# Current_Sinks.net
KiCad netlist of a schematic drawn in Altium Designer
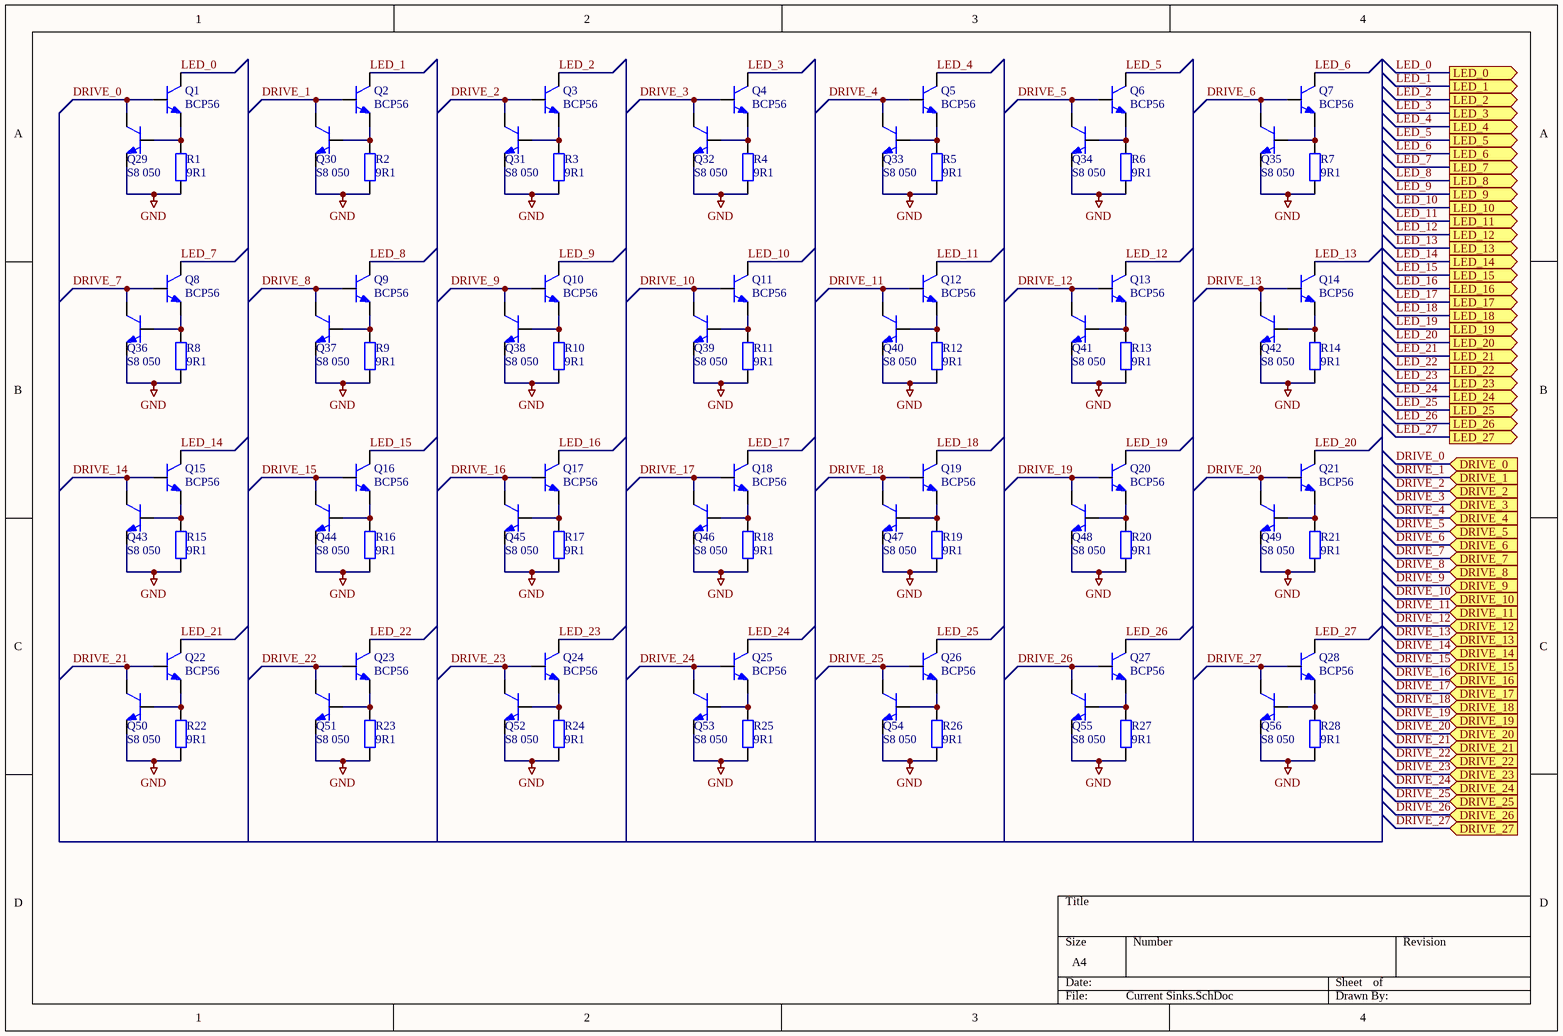
[diagram p0: Current Sinks.SchDoc]

(export (version "E")
  (design (tool "Eeschema 10.0.6"))
  (components
    (comp (ref "Q1")
      (value "BCP56")
      (footprint "SOT223")
      (description "BCP56 80 V, 1 A NPN medium power transistors")
      (libsource (lib "LED TAIL LIGHTS") (part "NPN"))
    )
    (comp (ref "Q2")
      (value "BCP56")
      (footprint "SOT223")
      (description "BCP56 80 V, 1 A NPN medium power transistors")
      (libsource (lib "LED TAIL LIGHTS") (part "NPN"))
    )
    (comp (ref "Q3")
      (value "BCP56")
      (footprint "SOT223")
      (description "BCP56 80 V, 1 A NPN medium power transistors")
      (libsource (lib "LED TAIL LIGHTS") (part "NPN"))
    )
    (comp (ref "Q4")
      (value "BCP56")
      (footprint "SOT223")
      (description "BCP56 80 V, 1 A NPN medium power transistors")
      (libsource (lib "LED TAIL LIGHTS") (part "NPN"))
    )
    (comp (ref "Q5")
      (value "BCP56")
      (footprint "SOT223")
      (description "BCP56 80 V, 1 A NPN medium power transistors")
      (libsource (lib "LED TAIL LIGHTS") (part "NPN"))
    )
    (comp (ref "Q6")
      (value "BCP56")
      (footprint "SOT223")
      (description "BCP56 80 V, 1 A NPN medium power transistors")
      (libsource (lib "LED TAIL LIGHTS") (part "NPN"))
    )
    (comp (ref "Q7")
      (value "BCP56")
      (footprint "SOT223")
      (description "BCP56 80 V, 1 A NPN medium power transistors")
      (libsource (lib "LED TAIL LIGHTS") (part "NPN"))
    )
    (comp (ref "Q8")
      (value "BCP56")
      (footprint "SOT223")
      (description "BCP56 80 V, 1 A NPN medium power transistors")
      (libsource (lib "LED TAIL LIGHTS") (part "NPN"))
    )
    (comp (ref "Q9")
      (value "BCP56")
      (footprint "SOT223")
      (description "BCP56 80 V, 1 A NPN medium power transistors")
      (libsource (lib "LED TAIL LIGHTS") (part "NPN"))
    )
    (comp (ref "Q10")
      (value "BCP56")
      (footprint "SOT223")
      (description "BCP56 80 V, 1 A NPN medium power transistors")
      (libsource (lib "LED TAIL LIGHTS") (part "NPN"))
    )
    (comp (ref "Q11")
      (value "BCP56")
      (footprint "SOT223")
      (description "BCP56 80 V, 1 A NPN medium power transistors")
      (libsource (lib "LED TAIL LIGHTS") (part "NPN"))
    )
    (comp (ref "Q12")
      (value "BCP56")
      (footprint "SOT223")
      (description "BCP56 80 V, 1 A NPN medium power transistors")
      (libsource (lib "LED TAIL LIGHTS") (part "NPN"))
    )
    (comp (ref "Q13")
      (value "BCP56")
      (footprint "SOT223")
      (description "BCP56 80 V, 1 A NPN medium power transistors")
      (libsource (lib "LED TAIL LIGHTS") (part "NPN"))
    )
    (comp (ref "Q14")
      (value "BCP56")
      (footprint "SOT223")
      (description "BCP56 80 V, 1 A NPN medium power transistors")
      (libsource (lib "LED TAIL LIGHTS") (part "NPN"))
    )
    (comp (ref "Q15")
      (value "BCP56")
      (footprint "SOT223")
      (description "BCP56 80 V, 1 A NPN medium power transistors")
      (libsource (lib "LED TAIL LIGHTS") (part "NPN"))
    )
    (comp (ref "Q16")
      (value "BCP56")
      (footprint "SOT223")
      (description "BCP56 80 V, 1 A NPN medium power transistors")
      (libsource (lib "LED TAIL LIGHTS") (part "NPN"))
    )
    (comp (ref "Q17")
      (value "BCP56")
      (footprint "SOT223")
      (description "BCP56 80 V, 1 A NPN medium power transistors")
      (libsource (lib "LED TAIL LIGHTS") (part "NPN"))
    )
    (comp (ref "Q18")
      (value "BCP56")
      (footprint "SOT223")
      (description "BCP56 80 V, 1 A NPN medium power transistors")
      (libsource (lib "LED TAIL LIGHTS") (part "NPN"))
    )
    (comp (ref "Q19")
      (value "BCP56")
      (footprint "SOT223")
      (description "BCP56 80 V, 1 A NPN medium power transistors")
      (libsource (lib "LED TAIL LIGHTS") (part "NPN"))
    )
    (comp (ref "Q20")
      (value "BCP56")
      (footprint "SOT223")
      (description "BCP56 80 V, 1 A NPN medium power transistors")
      (libsource (lib "LED TAIL LIGHTS") (part "NPN"))
    )
    (comp (ref "Q21")
      (value "BCP56")
      (footprint "SOT223")
      (description "BCP56 80 V, 1 A NPN medium power transistors")
      (libsource (lib "LED TAIL LIGHTS") (part "NPN"))
    )
    (comp (ref "Q22")
      (value "BCP56")
      (footprint "SOT223")
      (description "BCP56 80 V, 1 A NPN medium power transistors")
      (libsource (lib "LED TAIL LIGHTS") (part "NPN"))
    )
    (comp (ref "Q23")
      (value "BCP56")
      (footprint "SOT223")
      (description "BCP56 80 V, 1 A NPN medium power transistors")
      (libsource (lib "LED TAIL LIGHTS") (part "NPN"))
    )
    (comp (ref "Q24")
      (value "BCP56")
      (footprint "SOT223")
      (description "BCP56 80 V, 1 A NPN medium power transistors")
      (libsource (lib "LED TAIL LIGHTS") (part "NPN"))
    )
    (comp (ref "Q25")
      (value "BCP56")
      (footprint "SOT223")
      (description "BCP56 80 V, 1 A NPN medium power transistors")
      (libsource (lib "LED TAIL LIGHTS") (part "NPN"))
    )
    (comp (ref "Q26")
      (value "BCP56")
      (footprint "SOT223")
      (description "BCP56 80 V, 1 A NPN medium power transistors")
      (libsource (lib "LED TAIL LIGHTS") (part "NPN"))
    )
    (comp (ref "Q27")
      (value "BCP56")
      (footprint "SOT223")
      (description "BCP56 80 V, 1 A NPN medium power transistors")
      (libsource (lib "LED TAIL LIGHTS") (part "NPN"))
    )
    (comp (ref "Q28")
      (value "BCP56")
      (footprint "SOT223")
      (description "BCP56 80 V, 1 A NPN medium power transistors")
      (libsource (lib "LED TAIL LIGHTS") (part "NPN"))
    )
    (comp (ref "Q29")
      (value "S8 050")
      (footprint "SOT23-3L")
      (description "BCP56 80 V, 1 A NPN medium power transistors")
      (libsource (lib "LED TAIL LIGHTS") (part "NPN"))
    )
    (comp (ref "Q30")
      (value "S8 050")
      (footprint "SOT23-3L")
      (description "BCP56 80 V, 1 A NPN medium power transistors")
      (libsource (lib "LED TAIL LIGHTS") (part "NPN"))
    )
    (comp (ref "Q31")
      (value "S8 050")
      (footprint "SOT23-3L")
      (description "BCP56 80 V, 1 A NPN medium power transistors")
      (libsource (lib "LED TAIL LIGHTS") (part "NPN"))
    )
    (comp (ref "Q32")
      (value "S8 050")
      (footprint "SOT23-3L")
      (description "BCP56 80 V, 1 A NPN medium power transistors")
      (libsource (lib "LED TAIL LIGHTS") (part "NPN"))
    )
    (comp (ref "Q33")
      (value "S8 050")
      (footprint "SOT23-3L")
      (description "BCP56 80 V, 1 A NPN medium power transistors")
      (libsource (lib "LED TAIL LIGHTS") (part "NPN"))
    )
    (comp (ref "Q34")
      (value "S8 050")
      (footprint "SOT23-3L")
      (description "BCP56 80 V, 1 A NPN medium power transistors")
      (libsource (lib "LED TAIL LIGHTS") (part "NPN"))
    )
    (comp (ref "Q35")
      (value "S8 050")
      (footprint "SOT23-3L")
      (description "BCP56 80 V, 1 A NPN medium power transistors")
      (libsource (lib "LED TAIL LIGHTS") (part "NPN"))
    )
    (comp (ref "Q36")
      (value "S8 050")
      (footprint "SOT23-3L")
      (description "BCP56 80 V, 1 A NPN medium power transistors")
      (libsource (lib "LED TAIL LIGHTS") (part "NPN"))
    )
    (comp (ref "Q37")
      (value "S8 050")
      (footprint "SOT23-3L")
      (description "BCP56 80 V, 1 A NPN medium power transistors")
      (libsource (lib "LED TAIL LIGHTS") (part "NPN"))
    )
    (comp (ref "Q38")
      (value "S8 050")
      (footprint "SOT23-3L")
      (description "BCP56 80 V, 1 A NPN medium power transistors")
      (libsource (lib "LED TAIL LIGHTS") (part "NPN"))
    )
    (comp (ref "Q39")
      (value "S8 050")
      (footprint "SOT23-3L")
      (description "BCP56 80 V, 1 A NPN medium power transistors")
      (libsource (lib "LED TAIL LIGHTS") (part "NPN"))
    )
    (comp (ref "Q40")
      (value "S8 050")
      (footprint "SOT23-3L")
      (description "BCP56 80 V, 1 A NPN medium power transistors")
      (libsource (lib "LED TAIL LIGHTS") (part "NPN"))
    )
    (comp (ref "Q41")
      (value "S8 050")
      (footprint "SOT23-3L")
      (description "BCP56 80 V, 1 A NPN medium power transistors")
      (libsource (lib "LED TAIL LIGHTS") (part "NPN"))
    )
    (comp (ref "Q42")
      (value "S8 050")
      (footprint "SOT23-3L")
      (description "BCP56 80 V, 1 A NPN medium power transistors")
      (libsource (lib "LED TAIL LIGHTS") (part "NPN"))
    )
    (comp (ref "Q43")
      (value "S8 050")
      (footprint "SOT23-3L")
      (description "BCP56 80 V, 1 A NPN medium power transistors")
      (libsource (lib "LED TAIL LIGHTS") (part "NPN"))
    )
    (comp (ref "Q44")
      (value "S8 050")
      (footprint "SOT23-3L")
      (description "BCP56 80 V, 1 A NPN medium power transistors")
      (libsource (lib "LED TAIL LIGHTS") (part "NPN"))
    )
    (comp (ref "Q45")
      (value "S8 050")
      (footprint "SOT23-3L")
      (description "BCP56 80 V, 1 A NPN medium power transistors")
      (libsource (lib "LED TAIL LIGHTS") (part "NPN"))
    )
    (comp (ref "Q46")
      (value "S8 050")
      (footprint "SOT23-3L")
      (description "BCP56 80 V, 1 A NPN medium power transistors")
      (libsource (lib "LED TAIL LIGHTS") (part "NPN"))
    )
    (comp (ref "Q47")
      (value "S8 050")
      (footprint "SOT23-3L")
      (description "BCP56 80 V, 1 A NPN medium power transistors")
      (libsource (lib "LED TAIL LIGHTS") (part "NPN"))
    )
    (comp (ref "Q48")
      (value "S8 050")
      (footprint "SOT23-3L")
      (description "BCP56 80 V, 1 A NPN medium power transistors")
      (libsource (lib "LED TAIL LIGHTS") (part "NPN"))
    )
    (comp (ref "Q49")
      (value "S8 050")
      (footprint "SOT23-3L")
      (description "BCP56 80 V, 1 A NPN medium power transistors")
      (libsource (lib "LED TAIL LIGHTS") (part "NPN"))
    )
    (comp (ref "Q50")
      (value "S8 050")
      (footprint "SOT23-3L")
      (description "BCP56 80 V, 1 A NPN medium power transistors")
      (libsource (lib "LED TAIL LIGHTS") (part "NPN"))
    )
    (comp (ref "Q51")
      (value "S8 050")
      (footprint "SOT23-3L")
      (description "BCP56 80 V, 1 A NPN medium power transistors")
      (libsource (lib "LED TAIL LIGHTS") (part "NPN"))
    )
    (comp (ref "Q52")
      (value "S8 050")
      (footprint "SOT23-3L")
      (description "BCP56 80 V, 1 A NPN medium power transistors")
      (libsource (lib "LED TAIL LIGHTS") (part "NPN"))
    )
    (comp (ref "Q53")
      (value "S8 050")
      (footprint "SOT23-3L")
      (description "BCP56 80 V, 1 A NPN medium power transistors")
      (libsource (lib "LED TAIL LIGHTS") (part "NPN"))
    )
    (comp (ref "Q54")
      (value "S8 050")
      (footprint "SOT23-3L")
      (description "BCP56 80 V, 1 A NPN medium power transistors")
      (libsource (lib "LED TAIL LIGHTS") (part "NPN"))
    )
    (comp (ref "Q55")
      (value "S8 050")
      (footprint "SOT23-3L")
      (description "BCP56 80 V, 1 A NPN medium power transistors")
      (libsource (lib "LED TAIL LIGHTS") (part "NPN"))
    )
    (comp (ref "Q56")
      (value "S8 050")
      (footprint "SOT23-3L")
      (description "BCP56 80 V, 1 A NPN medium power transistors")
      (libsource (lib "LED TAIL LIGHTS") (part "NPN"))
    )
    (comp (ref "R1")
      (value "9R1")
      (footprint "RESISTOR 0805")
      (description "Resistor")
      (fields (field (name "PUBLISHER") "Altium Limited"))
      (libsource (lib "Miscellaneous Devices") (part "Res2"))
    )
    (comp (ref "R2")
      (value "9R1")
      (footprint "RESISTOR 0805")
      (description "Resistor")
      (fields (field (name "PUBLISHER") "Altium Limited"))
      (libsource (lib "Miscellaneous Devices") (part "Res2"))
    )
    (comp (ref "R3")
      (value "9R1")
      (footprint "RESISTOR 0805")
      (description "Resistor")
      (fields (field (name "PUBLISHER") "Altium Limited"))
      (libsource (lib "Miscellaneous Devices") (part "Res2"))
    )
    (comp (ref "R4")
      (value "9R1")
      (footprint "RESISTOR 0805")
      (description "Resistor")
      (fields (field (name "PUBLISHER") "Altium Limited"))
      (libsource (lib "Miscellaneous Devices") (part "Res2"))
    )
    (comp (ref "R5")
      (value "9R1")
      (footprint "RESISTOR 0805")
      (description "Resistor")
      (fields (field (name "PUBLISHER") "Altium Limited"))
      (libsource (lib "Miscellaneous Devices") (part "Res2"))
    )
    (comp (ref "R6")
      (value "9R1")
      (footprint "RESISTOR 0805")
      (description "Resistor")
      (fields (field (name "PUBLISHER") "Altium Limited"))
      (libsource (lib "Miscellaneous Devices") (part "Res2"))
    )
    (comp (ref "R7")
      (value "9R1")
      (footprint "RESISTOR 0805")
      (description "Resistor")
      (fields (field (name "PUBLISHER") "Altium Limited"))
      (libsource (lib "Miscellaneous Devices") (part "Res2"))
    )
    (comp (ref "R8")
      (value "9R1")
      (footprint "RESISTOR 0805")
      (description "Resistor")
      (fields (field (name "PUBLISHER") "Altium Limited"))
      (libsource (lib "Miscellaneous Devices") (part "Res2"))
    )
    (comp (ref "R9")
      (value "9R1")
      (footprint "RESISTOR 0805")
      (description "Resistor")
      (fields (field (name "PUBLISHER") "Altium Limited"))
      (libsource (lib "Miscellaneous Devices") (part "Res2"))
    )
    (comp (ref "R10")
      (value "9R1")
      (footprint "RESISTOR 0805")
      (description "Resistor")
      (fields (field (name "PUBLISHER") "Altium Limited"))
      (libsource (lib "Miscellaneous Devices") (part "Res2"))
    )
    (comp (ref "R11")
      (value "9R1")
      (footprint "RESISTOR 0805")
      (description "Resistor")
      (fields (field (name "PUBLISHER") "Altium Limited"))
      (libsource (lib "Miscellaneous Devices") (part "Res2"))
    )
    (comp (ref "R12")
      (value "9R1")
      (footprint "RESISTOR 0805")
      (description "Resistor")
      (fields (field (name "PUBLISHER") "Altium Limited"))
      (libsource (lib "Miscellaneous Devices") (part "Res2"))
    )
    (comp (ref "R13")
      (value "9R1")
      (footprint "RESISTOR 0805")
      (description "Resistor")
      (fields (field (name "PUBLISHER") "Altium Limited"))
      (libsource (lib "Miscellaneous Devices") (part "Res2"))
    )
    (comp (ref "R14")
      (value "9R1")
      (footprint "RESISTOR 0805")
      (description "Resistor")
      (fields (field (name "PUBLISHER") "Altium Limited"))
      (libsource (lib "Miscellaneous Devices") (part "Res2"))
    )
    (comp (ref "R15")
      (value "9R1")
      (footprint "RESISTOR 0805")
      (description "Resistor")
      (fields (field (name "PUBLISHER") "Altium Limited"))
      (libsource (lib "Miscellaneous Devices") (part "Res2"))
    )
    (comp (ref "R16")
      (value "9R1")
      (footprint "RESISTOR 0805")
      (description "Resistor")
      (fields (field (name "PUBLISHER") "Altium Limited"))
      (libsource (lib "Miscellaneous Devices") (part "Res2"))
    )
    (comp (ref "R17")
      (value "9R1")
      (footprint "RESISTOR 0805")
      (description "Resistor")
      (fields (field (name "PUBLISHER") "Altium Limited"))
      (libsource (lib "Miscellaneous Devices") (part "Res2"))
    )
    (comp (ref "R18")
      (value "9R1")
      (footprint "RESISTOR 0805")
      (description "Resistor")
      (fields (field (name "PUBLISHER") "Altium Limited"))
      (libsource (lib "Miscellaneous Devices") (part "Res2"))
    )
    (comp (ref "R19")
      (value "9R1")
      (footprint "RESISTOR 0805")
      (description "Resistor")
      (fields (field (name "PUBLISHER") "Altium Limited"))
      (libsource (lib "Miscellaneous Devices") (part "Res2"))
    )
    (comp (ref "R20")
      (value "9R1")
      (footprint "RESISTOR 0805")
      (description "Resistor")
      (fields (field (name "PUBLISHER") "Altium Limited"))
      (libsource (lib "Miscellaneous Devices") (part "Res2"))
    )
    (comp (ref "R21")
      (value "9R1")
      (footprint "RESISTOR 0805")
      (description "Resistor")
      (fields (field (name "PUBLISHER") "Altium Limited"))
      (libsource (lib "Miscellaneous Devices") (part "Res2"))
    )
    (comp (ref "R22")
      (value "9R1")
      (footprint "RESISTOR 0805")
      (description "Resistor")
      (fields (field (name "PUBLISHER") "Altium Limited"))
      (libsource (lib "Miscellaneous Devices") (part "Res2"))
    )
    (comp (ref "R23")
      (value "9R1")
      (footprint "RESISTOR 0805")
      (description "Resistor")
      (fields (field (name "PUBLISHER") "Altium Limited"))
      (libsource (lib "Miscellaneous Devices") (part "Res2"))
    )
    (comp (ref "R24")
      (value "9R1")
      (footprint "RESISTOR 0805")
      (description "Resistor")
      (fields (field (name "PUBLISHER") "Altium Limited"))
      (libsource (lib "Miscellaneous Devices") (part "Res2"))
    )
    (comp (ref "R25")
      (value "9R1")
      (footprint "RESISTOR 0805")
      (description "Resistor")
      (fields (field (name "PUBLISHER") "Altium Limited"))
      (libsource (lib "Miscellaneous Devices") (part "Res2"))
    )
    (comp (ref "R26")
      (value "9R1")
      (footprint "RESISTOR 0805")
      (description "Resistor")
      (fields (field (name "PUBLISHER") "Altium Limited"))
      (libsource (lib "Miscellaneous Devices") (part "Res2"))
    )
    (comp (ref "R27")
      (value "9R1")
      (footprint "RESISTOR 0805")
      (description "Resistor")
      (fields (field (name "PUBLISHER") "Altium Limited"))
      (libsource (lib "Miscellaneous Devices") (part "Res2"))
    )
    (comp (ref "R28")
      (value "9R1")
      (footprint "RESISTOR 0805")
      (description "Resistor")
      (fields (field (name "PUBLISHER") "Altium Limited"))
      (libsource (lib "Miscellaneous Devices") (part "Res2"))
    )
  )
  (nets
    (net (code "1") (name "/DRIVE_0") (class "Default")
      (node (ref "Q1") (pin "1") (pinfunction "B_1") (pintype "passive"))
      (node (ref "Q29") (pin "2") (pinfunction "C_2") (pintype "passive"))
    )
    (net (code "2") (name "/DRIVE_1") (class "Default")
      (node (ref "Q2") (pin "1") (pinfunction "B_1") (pintype "passive"))
      (node (ref "Q30") (pin "2") (pinfunction "C_2") (pintype "passive"))
    )
    (net (code "3") (name "/DRIVE_2") (class "Default")
      (node (ref "Q3") (pin "1") (pinfunction "B_1") (pintype "passive"))
      (node (ref "Q31") (pin "2") (pinfunction "C_2") (pintype "passive"))
    )
    (net (code "4") (name "/DRIVE_3") (class "Default")
      (node (ref "Q32") (pin "2") (pinfunction "C_2") (pintype "passive"))
      (node (ref "Q4") (pin "1") (pinfunction "B_1") (pintype "passive"))
    )
    (net (code "5") (name "/DRIVE_4") (class "Default")
      (node (ref "Q33") (pin "2") (pinfunction "C_2") (pintype "passive"))
      (node (ref "Q5") (pin "1") (pinfunction "B_1") (pintype "passive"))
    )
    (net (code "6") (name "/DRIVE_5") (class "Default")
      (node (ref "Q34") (pin "2") (pinfunction "C_2") (pintype "passive"))
      (node (ref "Q6") (pin "1") (pinfunction "B_1") (pintype "passive"))
    )
    (net (code "7") (name "/DRIVE_6") (class "Default")
      (node (ref "Q35") (pin "2") (pinfunction "C_2") (pintype "passive"))
      (node (ref "Q7") (pin "1") (pinfunction "B_1") (pintype "passive"))
    )
    (net (code "8") (name "/DRIVE_7") (class "Default")
      (node (ref "Q36") (pin "2") (pinfunction "C_2") (pintype "passive"))
      (node (ref "Q8") (pin "1") (pinfunction "B_1") (pintype "passive"))
    )
    (net (code "9") (name "/DRIVE_8") (class "Default")
      (node (ref "Q37") (pin "2") (pinfunction "C_2") (pintype "passive"))
      (node (ref "Q9") (pin "1") (pinfunction "B_1") (pintype "passive"))
    )
    (net (code "10") (name "/DRIVE_9") (class "Default")
      (node (ref "Q10") (pin "1") (pinfunction "B_1") (pintype "passive"))
      (node (ref "Q38") (pin "2") (pinfunction "C_2") (pintype "passive"))
    )
    (net (code "11") (name "/DRIVE_10") (class "Default")
      (node (ref "Q11") (pin "1") (pinfunction "B_1") (pintype "passive"))
      (node (ref "Q39") (pin "2") (pinfunction "C_2") (pintype "passive"))
    )
    (net (code "12") (name "/DRIVE_11") (class "Default")
      (node (ref "Q12") (pin "1") (pinfunction "B_1") (pintype "passive"))
      (node (ref "Q40") (pin "2") (pinfunction "C_2") (pintype "passive"))
    )
    (net (code "13") (name "/DRIVE_12") (class "Default")
      (node (ref "Q13") (pin "1") (pinfunction "B_1") (pintype "passive"))
      (node (ref "Q41") (pin "2") (pinfunction "C_2") (pintype "passive"))
    )
    (net (code "14") (name "/DRIVE_13") (class "Default")
      (node (ref "Q14") (pin "1") (pinfunction "B_1") (pintype "passive"))
      (node (ref "Q42") (pin "2") (pinfunction "C_2") (pintype "passive"))
    )
    (net (code "15") (name "/DRIVE_14") (class "Default")
      (node (ref "Q15") (pin "1") (pinfunction "B_1") (pintype "passive"))
      (node (ref "Q43") (pin "2") (pinfunction "C_2") (pintype "passive"))
    )
    (net (code "16") (name "/DRIVE_15") (class "Default")
      (node (ref "Q16") (pin "1") (pinfunction "B_1") (pintype "passive"))
      (node (ref "Q44") (pin "2") (pinfunction "C_2") (pintype "passive"))
    )
    (net (code "17") (name "/DRIVE_16") (class "Default")
      (node (ref "Q17") (pin "1") (pinfunction "B_1") (pintype "passive"))
      (node (ref "Q45") (pin "2") (pinfunction "C_2") (pintype "passive"))
    )
    (net (code "18") (name "/DRIVE_17") (class "Default")
      (node (ref "Q18") (pin "1") (pinfunction "B_1") (pintype "passive"))
      (node (ref "Q46") (pin "2") (pinfunction "C_2") (pintype "passive"))
    )
    (net (code "19") (name "/DRIVE_18") (class "Default")
      (node (ref "Q19") (pin "1") (pinfunction "B_1") (pintype "passive"))
      (node (ref "Q47") (pin "2") (pinfunction "C_2") (pintype "passive"))
    )
    (net (code "20") (name "/DRIVE_19") (class "Default")
      (node (ref "Q20") (pin "1") (pinfunction "B_1") (pintype "passive"))
      (node (ref "Q48") (pin "2") (pinfunction "C_2") (pintype "passive"))
    )
    (net (code "21") (name "/DRIVE_20") (class "Default")
      (node (ref "Q21") (pin "1") (pinfunction "B_1") (pintype "passive"))
      (node (ref "Q49") (pin "2") (pinfunction "C_2") (pintype "passive"))
    )
    (net (code "22") (name "/DRIVE_21") (class "Default")
      (node (ref "Q22") (pin "1") (pinfunction "B_1") (pintype "passive"))
      (node (ref "Q50") (pin "2") (pinfunction "C_2") (pintype "passive"))
    )
    (net (code "23") (name "/DRIVE_22") (class "Default")
      (node (ref "Q23") (pin "1") (pinfunction "B_1") (pintype "passive"))
      (node (ref "Q51") (pin "2") (pinfunction "C_2") (pintype "passive"))
    )
    (net (code "24") (name "/DRIVE_23") (class "Default")
      (node (ref "Q24") (pin "1") (pinfunction "B_1") (pintype "passive"))
      (node (ref "Q52") (pin "2") (pinfunction "C_2") (pintype "passive"))
    )
    (net (code "25") (name "/DRIVE_24") (class "Default")
      (node (ref "Q25") (pin "1") (pinfunction "B_1") (pintype "passive"))
      (node (ref "Q53") (pin "2") (pinfunction "C_2") (pintype "passive"))
    )
    (net (code "26") (name "/DRIVE_25") (class "Default")
      (node (ref "Q26") (pin "1") (pinfunction "B_1") (pintype "passive"))
      (node (ref "Q54") (pin "2") (pinfunction "C_2") (pintype "passive"))
    )
    (net (code "27") (name "/DRIVE_26") (class "Default")
      (node (ref "Q27") (pin "1") (pinfunction "B_1") (pintype "passive"))
      (node (ref "Q55") (pin "2") (pinfunction "C_2") (pintype "passive"))
    )
    (net (code "28") (name "/DRIVE_27") (class "Default")
      (node (ref "Q28") (pin "1") (pinfunction "B_1") (pintype "passive"))
      (node (ref "Q56") (pin "2") (pinfunction "C_2") (pintype "passive"))
    )
    (net (code "29") (name "/LED_0") (class "Default")
      (node (ref "Q1") (pin "2") (pinfunction "C_2") (pintype "passive"))
    )
    (net (code "30") (name "/LED_1") (class "Default")
      (node (ref "Q2") (pin "2") (pinfunction "C_2") (pintype "passive"))
    )
    (net (code "31") (name "/LED_2") (class "Default")
      (node (ref "Q3") (pin "2") (pinfunction "C_2") (pintype "passive"))
    )
    (net (code "32") (name "/LED_3") (class "Default")
      (node (ref "Q4") (pin "2") (pinfunction "C_2") (pintype "passive"))
    )
    (net (code "33") (name "/LED_4") (class "Default")
      (node (ref "Q5") (pin "2") (pinfunction "C_2") (pintype "passive"))
    )
    (net (code "34") (name "/LED_5") (class "Default")
      (node (ref "Q6") (pin "2") (pinfunction "C_2") (pintype "passive"))
    )
    (net (code "35") (name "/LED_6") (class "Default")
      (node (ref "Q7") (pin "2") (pinfunction "C_2") (pintype "passive"))
    )
    (net (code "36") (name "/LED_7") (class "Default")
      (node (ref "Q8") (pin "2") (pinfunction "C_2") (pintype "passive"))
    )
    (net (code "37") (name "/LED_8") (class "Default")
      (node (ref "Q9") (pin "2") (pinfunction "C_2") (pintype "passive"))
    )
    (net (code "38") (name "/LED_9") (class "Default")
      (node (ref "Q10") (pin "2") (pinfunction "C_2") (pintype "passive"))
    )
    (net (code "39") (name "/LED_10") (class "Default")
      (node (ref "Q11") (pin "2") (pinfunction "C_2") (pintype "passive"))
    )
    (net (code "40") (name "/LED_11") (class "Default")
      (node (ref "Q12") (pin "2") (pinfunction "C_2") (pintype "passive"))
    )
    (net (code "41") (name "/LED_12") (class "Default")
      (node (ref "Q13") (pin "2") (pinfunction "C_2") (pintype "passive"))
    )
    (net (code "42") (name "/LED_13") (class "Default")
      (node (ref "Q14") (pin "2") (pinfunction "C_2") (pintype "passive"))
    )
    (net (code "43") (name "/LED_14") (class "Default")
      (node (ref "Q15") (pin "2") (pinfunction "C_2") (pintype "passive"))
    )
    (net (code "44") (name "/LED_15") (class "Default")
      (node (ref "Q16") (pin "2") (pinfunction "C_2") (pintype "passive"))
    )
    (net (code "45") (name "/LED_16") (class "Default")
      (node (ref "Q17") (pin "2") (pinfunction "C_2") (pintype "passive"))
    )
    (net (code "46") (name "/LED_17") (class "Default")
      (node (ref "Q18") (pin "2") (pinfunction "C_2") (pintype "passive"))
    )
    (net (code "47") (name "/LED_18") (class "Default")
      (node (ref "Q19") (pin "2") (pinfunction "C_2") (pintype "passive"))
    )
    (net (code "48") (name "/LED_19") (class "Default")
      (node (ref "Q20") (pin "2") (pinfunction "C_2") (pintype "passive"))
    )
    (net (code "49") (name "/LED_20") (class "Default")
      (node (ref "Q21") (pin "2") (pinfunction "C_2") (pintype "passive"))
    )
    (net (code "50") (name "/LED_21") (class "Default")
      (node (ref "Q22") (pin "2") (pinfunction "C_2") (pintype "passive"))
    )
    (net (code "51") (name "/LED_22") (class "Default")
      (node (ref "Q23") (pin "2") (pinfunction "C_2") (pintype "passive"))
    )
    (net (code "52") (name "/LED_23") (class "Default")
      (node (ref "Q24") (pin "2") (pinfunction "C_2") (pintype "passive"))
    )
    (net (code "53") (name "/LED_24") (class "Default")
      (node (ref "Q25") (pin "2") (pinfunction "C_2") (pintype "passive"))
    )
    (net (code "54") (name "/LED_25") (class "Default")
      (node (ref "Q26") (pin "2") (pinfunction "C_2") (pintype "passive"))
    )
    (net (code "55") (name "/LED_26") (class "Default")
      (node (ref "Q27") (pin "2") (pinfunction "C_2") (pintype "passive"))
    )
    (net (code "56") (name "/LED_27") (class "Default")
      (node (ref "Q28") (pin "2") (pinfunction "C_2") (pintype "passive"))
    )
    (net (code "57") (name "GND") (class "Default")
      (node (ref "Q29") (pin "3") (pinfunction "E_3") (pintype "passive"))
      (node (ref "Q30") (pin "3") (pinfunction "E_3") (pintype "passive"))
      (node (ref "Q31") (pin "3") (pinfunction "E_3") (pintype "passive"))
      (node (ref "Q32") (pin "3") (pinfunction "E_3") (pintype "passive"))
      (node (ref "Q33") (pin "3") (pinfunction "E_3") (pintype "passive"))
      (node (ref "Q34") (pin "3") (pinfunction "E_3") (pintype "passive"))
      (node (ref "Q35") (pin "3") (pinfunction "E_3") (pintype "passive"))
      (node (ref "Q36") (pin "3") (pinfunction "E_3") (pintype "passive"))
      (node (ref "Q37") (pin "3") (pinfunction "E_3") (pintype "passive"))
      (node (ref "Q38") (pin "3") (pinfunction "E_3") (pintype "passive"))
      (node (ref "Q39") (pin "3") (pinfunction "E_3") (pintype "passive"))
      (node (ref "Q40") (pin "3") (pinfunction "E_3") (pintype "passive"))
      (node (ref "Q41") (pin "3") (pinfunction "E_3") (pintype "passive"))
      (node (ref "Q42") (pin "3") (pinfunction "E_3") (pintype "passive"))
      (node (ref "Q43") (pin "3") (pinfunction "E_3") (pintype "passive"))
      (node (ref "Q44") (pin "3") (pinfunction "E_3") (pintype "passive"))
      (node (ref "Q45") (pin "3") (pinfunction "E_3") (pintype "passive"))
      (node (ref "Q46") (pin "3") (pinfunction "E_3") (pintype "passive"))
      (node (ref "Q47") (pin "3") (pinfunction "E_3") (pintype "passive"))
      (node (ref "Q48") (pin "3") (pinfunction "E_3") (pintype "passive"))
      (node (ref "Q49") (pin "3") (pinfunction "E_3") (pintype "passive"))
      (node (ref "Q50") (pin "3") (pinfunction "E_3") (pintype "passive"))
      (node (ref "Q51") (pin "3") (pinfunction "E_3") (pintype "passive"))
      (node (ref "Q52") (pin "3") (pinfunction "E_3") (pintype "passive"))
      (node (ref "Q53") (pin "3") (pinfunction "E_3") (pintype "passive"))
      (node (ref "Q54") (pin "3") (pinfunction "E_3") (pintype "passive"))
      (node (ref "Q55") (pin "3") (pinfunction "E_3") (pintype "passive"))
      (node (ref "Q56") (pin "3") (pinfunction "E_3") (pintype "passive"))
      (node (ref "R1") (pin "1") (pinfunction "1_1") (pintype "passive"))
      (node (ref "R10") (pin "1") (pinfunction "1_1") (pintype "passive"))
      (node (ref "R11") (pin "1") (pinfunction "1_1") (pintype "passive"))
      (node (ref "R12") (pin "1") (pinfunction "1_1") (pintype "passive"))
      (node (ref "R13") (pin "1") (pinfunction "1_1") (pintype "passive"))
      (node (ref "R14") (pin "1") (pinfunction "1_1") (pintype "passive"))
      (node (ref "R15") (pin "1") (pinfunction "1_1") (pintype "passive"))
      (node (ref "R16") (pin "1") (pinfunction "1_1") (pintype "passive"))
      (node (ref "R17") (pin "1") (pinfunction "1_1") (pintype "passive"))
      (node (ref "R18") (pin "1") (pinfunction "1_1") (pintype "passive"))
      (node (ref "R19") (pin "1") (pinfunction "1_1") (pintype "passive"))
      (node (ref "R2") (pin "1") (pinfunction "1_1") (pintype "passive"))
      (node (ref "R20") (pin "1") (pinfunction "1_1") (pintype "passive"))
      (node (ref "R21") (pin "1") (pinfunction "1_1") (pintype "passive"))
      (node (ref "R22") (pin "1") (pinfunction "1_1") (pintype "passive"))
      (node (ref "R23") (pin "1") (pinfunction "1_1") (pintype "passive"))
      (node (ref "R24") (pin "1") (pinfunction "1_1") (pintype "passive"))
      (node (ref "R25") (pin "1") (pinfunction "1_1") (pintype "passive"))
      (node (ref "R26") (pin "1") (pinfunction "1_1") (pintype "passive"))
      (node (ref "R27") (pin "1") (pinfunction "1_1") (pintype "passive"))
      (node (ref "R28") (pin "1") (pinfunction "1_1") (pintype "passive"))
      (node (ref "R3") (pin "1") (pinfunction "1_1") (pintype "passive"))
      (node (ref "R4") (pin "1") (pinfunction "1_1") (pintype "passive"))
      (node (ref "R5") (pin "1") (pinfunction "1_1") (pintype "passive"))
      (node (ref "R6") (pin "1") (pinfunction "1_1") (pintype "passive"))
      (node (ref "R7") (pin "1") (pinfunction "1_1") (pintype "passive"))
      (node (ref "R8") (pin "1") (pinfunction "1_1") (pintype "passive"))
      (node (ref "R9") (pin "1") (pinfunction "1_1") (pintype "passive"))
    )
    (net (code "58") (name "Net-(Q1-E)") (class "Default")
      (node (ref "Q1") (pin "3") (pinfunction "E_3") (pintype "passive"))
      (node (ref "Q29") (pin "1") (pinfunction "B_1") (pintype "passive"))
      (node (ref "R1") (pin "2") (pinfunction "2_2") (pintype "passive"))
    )
    (net (code "59") (name "Net-(Q2-E)") (class "Default")
      (node (ref "Q2") (pin "3") (pinfunction "E_3") (pintype "passive"))
      (node (ref "Q30") (pin "1") (pinfunction "B_1") (pintype "passive"))
      (node (ref "R2") (pin "2") (pinfunction "2_2") (pintype "passive"))
    )
    (net (code "60") (name "Net-(Q3-E)") (class "Default")
      (node (ref "Q3") (pin "3") (pinfunction "E_3") (pintype "passive"))
      (node (ref "Q31") (pin "1") (pinfunction "B_1") (pintype "passive"))
      (node (ref "R3") (pin "2") (pinfunction "2_2") (pintype "passive"))
    )
    (net (code "61") (name "Net-(Q10-E)") (class "Default")
      (node (ref "Q10") (pin "3") (pinfunction "E_3") (pintype "passive"))
      (node (ref "Q38") (pin "1") (pinfunction "B_1") (pintype "passive"))
      (node (ref "R10") (pin "2") (pinfunction "2_2") (pintype "passive"))
    )
    (net (code "62") (name "Net-(Q11-E)") (class "Default")
      (node (ref "Q11") (pin "3") (pinfunction "E_3") (pintype "passive"))
      (node (ref "Q39") (pin "1") (pinfunction "B_1") (pintype "passive"))
      (node (ref "R11") (pin "2") (pinfunction "2_2") (pintype "passive"))
    )
    (net (code "63") (name "Net-(Q12-E)") (class "Default")
      (node (ref "Q12") (pin "3") (pinfunction "E_3") (pintype "passive"))
      (node (ref "Q40") (pin "1") (pinfunction "B_1") (pintype "passive"))
      (node (ref "R12") (pin "2") (pinfunction "2_2") (pintype "passive"))
    )
    (net (code "64") (name "Net-(Q13-E)") (class "Default")
      (node (ref "Q13") (pin "3") (pinfunction "E_3") (pintype "passive"))
      (node (ref "Q41") (pin "1") (pinfunction "B_1") (pintype "passive"))
      (node (ref "R13") (pin "2") (pinfunction "2_2") (pintype "passive"))
    )
    (net (code "65") (name "Net-(Q14-E)") (class "Default")
      (node (ref "Q14") (pin "3") (pinfunction "E_3") (pintype "passive"))
      (node (ref "Q42") (pin "1") (pinfunction "B_1") (pintype "passive"))
      (node (ref "R14") (pin "2") (pinfunction "2_2") (pintype "passive"))
    )
    (net (code "66") (name "Net-(Q15-E)") (class "Default")
      (node (ref "Q15") (pin "3") (pinfunction "E_3") (pintype "passive"))
      (node (ref "Q43") (pin "1") (pinfunction "B_1") (pintype "passive"))
      (node (ref "R15") (pin "2") (pinfunction "2_2") (pintype "passive"))
    )
    (net (code "67") (name "Net-(Q16-E)") (class "Default")
      (node (ref "Q16") (pin "3") (pinfunction "E_3") (pintype "passive"))
      (node (ref "Q44") (pin "1") (pinfunction "B_1") (pintype "passive"))
      (node (ref "R16") (pin "2") (pinfunction "2_2") (pintype "passive"))
    )
    (net (code "68") (name "Net-(Q17-E)") (class "Default")
      (node (ref "Q17") (pin "3") (pinfunction "E_3") (pintype "passive"))
      (node (ref "Q45") (pin "1") (pinfunction "B_1") (pintype "passive"))
      (node (ref "R17") (pin "2") (pinfunction "2_2") (pintype "passive"))
    )
    (net (code "69") (name "Net-(Q18-E)") (class "Default")
      (node (ref "Q18") (pin "3") (pinfunction "E_3") (pintype "passive"))
      (node (ref "Q46") (pin "1") (pinfunction "B_1") (pintype "passive"))
      (node (ref "R18") (pin "2") (pinfunction "2_2") (pintype "passive"))
    )
    (net (code "70") (name "Net-(Q19-E)") (class "Default")
      (node (ref "Q19") (pin "3") (pinfunction "E_3") (pintype "passive"))
      (node (ref "Q47") (pin "1") (pinfunction "B_1") (pintype "passive"))
      (node (ref "R19") (pin "2") (pinfunction "2_2") (pintype "passive"))
    )
    (net (code "71") (name "Net-(Q20-E)") (class "Default")
      (node (ref "Q20") (pin "3") (pinfunction "E_3") (pintype "passive"))
      (node (ref "Q48") (pin "1") (pinfunction "B_1") (pintype "passive"))
      (node (ref "R20") (pin "2") (pinfunction "2_2") (pintype "passive"))
    )
    (net (code "72") (name "Net-(Q21-E)") (class "Default")
      (node (ref "Q21") (pin "3") (pinfunction "E_3") (pintype "passive"))
      (node (ref "Q49") (pin "1") (pinfunction "B_1") (pintype "passive"))
      (node (ref "R21") (pin "2") (pinfunction "2_2") (pintype "passive"))
    )
    (net (code "73") (name "Net-(Q22-E)") (class "Default")
      (node (ref "Q22") (pin "3") (pinfunction "E_3") (pintype "passive"))
      (node (ref "Q50") (pin "1") (pinfunction "B_1") (pintype "passive"))
      (node (ref "R22") (pin "2") (pinfunction "2_2") (pintype "passive"))
    )
    (net (code "74") (name "Net-(Q23-E)") (class "Default")
      (node (ref "Q23") (pin "3") (pinfunction "E_3") (pintype "passive"))
      (node (ref "Q51") (pin "1") (pinfunction "B_1") (pintype "passive"))
      (node (ref "R23") (pin "2") (pinfunction "2_2") (pintype "passive"))
    )
    (net (code "75") (name "Net-(Q24-E)") (class "Default")
      (node (ref "Q24") (pin "3") (pinfunction "E_3") (pintype "passive"))
      (node (ref "Q52") (pin "1") (pinfunction "B_1") (pintype "passive"))
      (node (ref "R24") (pin "2") (pinfunction "2_2") (pintype "passive"))
    )
    (net (code "76") (name "Net-(Q25-E)") (class "Default")
      (node (ref "Q25") (pin "3") (pinfunction "E_3") (pintype "passive"))
      (node (ref "Q53") (pin "1") (pinfunction "B_1") (pintype "passive"))
      (node (ref "R25") (pin "2") (pinfunction "2_2") (pintype "passive"))
    )
    (net (code "77") (name "Net-(Q26-E)") (class "Default")
      (node (ref "Q26") (pin "3") (pinfunction "E_3") (pintype "passive"))
      (node (ref "Q54") (pin "1") (pinfunction "B_1") (pintype "passive"))
      (node (ref "R26") (pin "2") (pinfunction "2_2") (pintype "passive"))
    )
    (net (code "78") (name "Net-(Q27-E)") (class "Default")
      (node (ref "Q27") (pin "3") (pinfunction "E_3") (pintype "passive"))
      (node (ref "Q55") (pin "1") (pinfunction "B_1") (pintype "passive"))
      (node (ref "R27") (pin "2") (pinfunction "2_2") (pintype "passive"))
    )
    (net (code "79") (name "Net-(Q28-E)") (class "Default")
      (node (ref "Q28") (pin "3") (pinfunction "E_3") (pintype "passive"))
      (node (ref "Q56") (pin "1") (pinfunction "B_1") (pintype "passive"))
      (node (ref "R28") (pin "2") (pinfunction "2_2") (pintype "passive"))
    )
    (net (code "80") (name "Net-(Q32-B)") (class "Default")
      (node (ref "Q32") (pin "1") (pinfunction "B_1") (pintype "passive"))
      (node (ref "Q4") (pin "3") (pinfunction "E_3") (pintype "passive"))
      (node (ref "R4") (pin "2") (pinfunction "2_2") (pintype "passive"))
    )
    (net (code "81") (name "Net-(Q33-B)") (class "Default")
      (node (ref "Q33") (pin "1") (pinfunction "B_1") (pintype "passive"))
      (node (ref "Q5") (pin "3") (pinfunction "E_3") (pintype "passive"))
      (node (ref "R5") (pin "2") (pinfunction "2_2") (pintype "passive"))
    )
    (net (code "82") (name "Net-(Q34-B)") (class "Default")
      (node (ref "Q34") (pin "1") (pinfunction "B_1") (pintype "passive"))
      (node (ref "Q6") (pin "3") (pinfunction "E_3") (pintype "passive"))
      (node (ref "R6") (pin "2") (pinfunction "2_2") (pintype "passive"))
    )
    (net (code "83") (name "Net-(Q35-B)") (class "Default")
      (node (ref "Q35") (pin "1") (pinfunction "B_1") (pintype "passive"))
      (node (ref "Q7") (pin "3") (pinfunction "E_3") (pintype "passive"))
      (node (ref "R7") (pin "2") (pinfunction "2_2") (pintype "passive"))
    )
    (net (code "84") (name "Net-(Q36-B)") (class "Default")
      (node (ref "Q36") (pin "1") (pinfunction "B_1") (pintype "passive"))
      (node (ref "Q8") (pin "3") (pinfunction "E_3") (pintype "passive"))
      (node (ref "R8") (pin "2") (pinfunction "2_2") (pintype "passive"))
    )
    (net (code "85") (name "Net-(Q37-B)") (class "Default")
      (node (ref "Q37") (pin "1") (pinfunction "B_1") (pintype "passive"))
      (node (ref "Q9") (pin "3") (pinfunction "E_3") (pintype "passive"))
      (node (ref "R9") (pin "2") (pinfunction "2_2") (pintype "passive"))
    )
  )
)
